# Power_Supply.net
KiCad netlist of a schematic drawn in Altium Designer
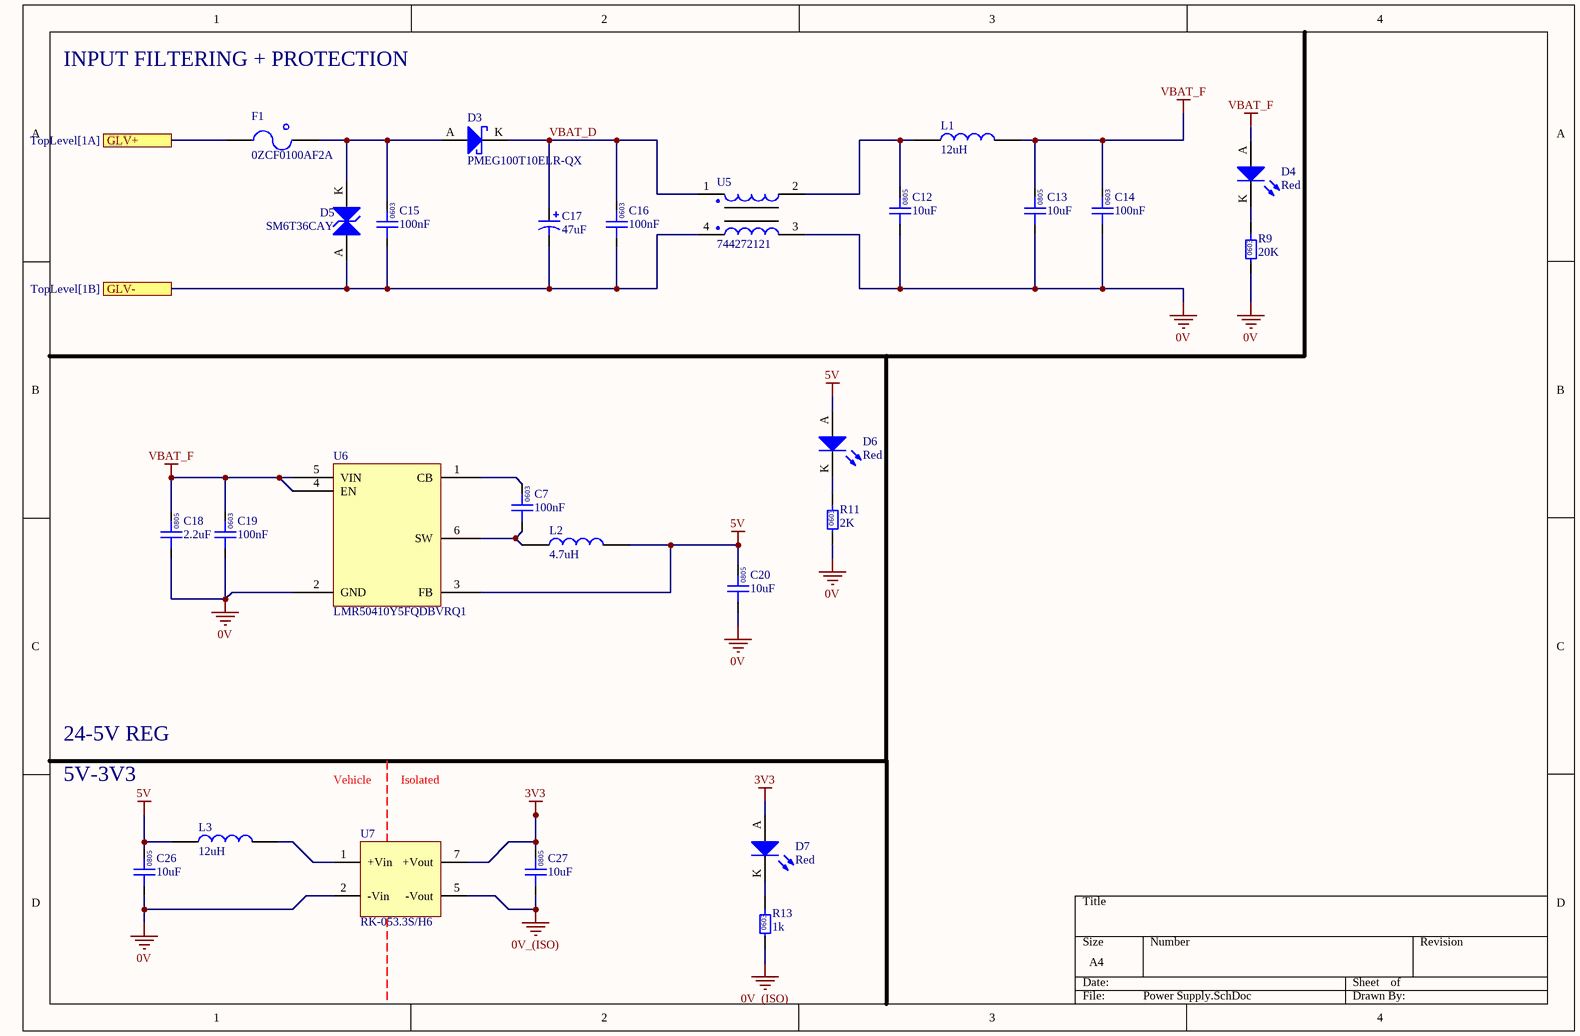
[diagram p0: Power Supply.SchDoc]

(export (version "E")
  (design (tool "Eeschema 10.0.6"))
  (components
    (comp (ref "C7")
      (value "100nF")
      (footprint "0603")
      (fields
        (field (name "PART NUMBER") "GCM188L81H104KA57D")
        (field (name "MANUFACTURER") "muRata")
        (field (name "TOLERANCE") "±10%")
      )
      (libsource (lib "ts_standard_library") (part "Capacitor 0603"))
    )
    (comp (ref "C12")
      (value "10uF")
      (footprint "0805")
      (fields
        (field (name "PART NUMBER") "GRM21BR6YA106KE43L")
        (field (name "MANUFACTURER") "muRata")
        (field (name "TOLERANCE") "10%")
      )
      (libsource (lib "ts_standard_library") (part "Capacitor 0805"))
    )
    (comp (ref "C13")
      (value "10uF")
      (footprint "0805")
      (fields
        (field (name "PART NUMBER") "GRM21BR6YA106KE43L")
        (field (name "MANUFACTURER") "muRata")
        (field (name "TOLERANCE") "10%")
      )
      (libsource (lib "ts_standard_library") (part "Capacitor 0805"))
    )
    (comp (ref "C14")
      (value "100nF")
      (footprint "0603")
      (fields
        (field (name "PART NUMBER") "GCM188L81H104KA57D")
        (field (name "MANUFACTURER") "muRata")
        (field (name "TOLERANCE") "±10%")
      )
      (libsource (lib "ts_standard_library") (part "Capacitor 0603"))
    )
    (comp (ref "C15")
      (value "100nF")
      (footprint "0603")
      (fields
        (field (name "PART NUMBER") "GCM188L81H104KA57D")
        (field (name "MANUFACTURER") "muRata")
        (field (name "TOLERANCE") "±10%")
      )
      (libsource (lib "ts_standard_library") (part "Capacitor 0603"))
    )
    (comp (ref "C16")
      (value "100nF")
      (footprint "0603")
      (fields
        (field (name "PART NUMBER") "GCM188L81H104KA57D")
        (field (name "MANUFACTURER") "muRata")
        (field (name "TOLERANCE") "±10%")
      )
      (libsource (lib "ts_standard_library") (part "Capacitor 0603"))
    )
    (comp (ref "C17")
      (value "47uF")
      (footprint "CHEMI-CON ELCO")
      (fields (field (name "PART NUMBER") "HHXA350ARA470MF61G"))
      (libsource (lib "ts_standard_library") (part "Capacitor (Polarised)"))
    )
    (comp (ref "C18")
      (value "2.2uF")
      (footprint "0805")
      (fields
        (field (name "PART NUMBER") "GRM21BR71E225KE11L")
        (field (name "MANUFACTURER") "Murata Electronics")
        (field (name "TOLERANCE") "±10%")
      )
      (libsource (lib "ts_standard_library") (part "Capacitor 0805"))
    )
    (comp (ref "C19")
      (value "100nF")
      (footprint "0603")
      (fields
        (field (name "PART NUMBER") "GCM188L81H104KA57D")
        (field (name "MANUFACTURER") "muRata")
        (field (name "TOLERANCE") "±10%")
      )
      (libsource (lib "ts_standard_library") (part "Capacitor 0603"))
    )
    (comp (ref "C20")
      (value "10uF")
      (footprint "0805")
      (fields
        (field (name "PART NUMBER") "GRM21BR6YA106KE43L")
        (field (name "MANUFACTURER") "muRata")
        (field (name "TOLERANCE") "10%")
      )
      (libsource (lib "ts_standard_library") (part "Capacitor 0805"))
    )
    (comp (ref "C26")
      (value "10uF")
      (footprint "0805")
      (fields
        (field (name "PART NUMBER") "GRM21BR6YA106KE43L")
        (field (name "MANUFACTURER") "muRata")
        (field (name "TOLERANCE") "10%")
      )
      (libsource (lib "ts_standard_library") (part "Capacitor 0805"))
    )
    (comp (ref "C27")
      (value "10uF")
      (footprint "0805")
      (fields
        (field (name "PART NUMBER") "GRM21BR6YA106KE43L")
        (field (name "MANUFACTURER") "muRata")
        (field (name "TOLERANCE") "10%")
      )
      (libsource (lib "ts_standard_library") (part "Capacitor 0805"))
    )
    (comp (ref "D3")
      (value "PMEG100T10ELR-QX")
      (footprint "NXP SOD123W")
      (fields
        (field (name "MANUFACTURER") "Nexperia USA Inc.")
        (field (name "DIGIKEY PART NUMBER") "1727-PMEG100T10ELR-QXCT-ND")
      )
      (libsource (lib "ts_standard_library") (part "Diode (Schottky)"))
    )
    (comp (ref "D4")
      (value "Red")
      (footprint "0805 LED")
      (description "Red LED Indication - Discrete 1.75V 0805 (2012 Metric)")
      (fields (field (name "PART NUMBER") "SML-210LTT86") (field (name "MANUFACTURER") "ROHM Semiconductor"))
      (libsource (lib "ts_standard_library") (part "LED"))
    )
    (comp (ref "D5")
      (value "SM6T36CAY")
      (footprint "ST SMB DIODE")
      (fields
        (field (name "MANUFACTURER") "STMicroelectronics")
        (field (name "DIGIKEY PART NUMBER") "497-10804-1-ND")
      )
      (libsource (lib "ts_standard_library") (part "TVS (Bidirectional)"))
    )
    (comp (ref "D6")
      (value "Red")
      (footprint "0805 LED")
      (description "Red LED Indication - Discrete 1.75V 0805 (2012 Metric)")
      (fields (field (name "PART NUMBER") "SML-210LTT86") (field (name "MANUFACTURER") "ROHM Semiconductor"))
      (libsource (lib "ts_standard_library") (part "LED"))
    )
    (comp (ref "D7")
      (value "Red")
      (footprint "0805 LED")
      (description "Red LED Indication - Discrete 1.75V 0805 (2012 Metric)")
      (fields (field (name "PART NUMBER") "SML-210LTT86") (field (name "MANUFACTURER") "ROHM Semiconductor"))
      (libsource (lib "ts_standard_library") (part "LED"))
    )
    (comp (ref "F1")
      (value "0ZCF0100AF2A")
      (footprint "2920")
      (description "PTC RESET FUSE 60V 1A 292")
      (fields
        (field (name "MANUFACTURER") "Littelfuse Inc.")
        (field (name "DIGIKEY PART NUMBER") "507-2070-1-ND")
      )
      (libsource (lib "ts_standard_library") (part "PTC Fuse"))
    )
    (comp (ref "L1")
      (value "12uH")
      (footprint "1812")
      (fields
        (field (name "PART NUMBER") "RLS-126")
        (field (name "MANUFACTURER") "Recom")
        (field (name "TOLERANCE") "0.2")
      )
      (libsource (lib "ts_20-standard-library") (part "Inductor"))
    )
    (comp (ref "L2")
      (value "4.7uH")
      (footprint "SRN3015TA-4R7M")
      (fields
        (field (name "PART NUMBER") "SRN4018-4R7M")
        (field (name "MANUFACTURER") "Bourns")
        (field (name "TOLERANCE") "0.2")
      )
      (libsource (lib "ts_standard_library") (part "Inductor"))
    )
    (comp (ref "L3")
      (value "12uH")
      (footprint "1812")
      (fields
        (field (name "PART NUMBER") "RLS-126")
        (field (name "MANUFACTURER") "Recom")
        (field (name "TOLERANCE") "0.2")
      )
      (libsource (lib "ts_standard_library") (part "Inductor"))
    )
    (comp (ref "R9")
      (value "20K")
      (footprint "0603")
      (fields
        (field (name "PART NUMBER") "RC0603FR-0720KL")
        (field (name "MANUFACTURER") "YAGEO")
        (field (name "TOLERANCE") "0.01")
      )
      (libsource (lib "ts_standard_library") (part "Resistor 0603"))
    )
    (comp (ref "R11")
      (value "2K")
      (footprint "0603")
      (fields
        (field (name "PART NUMBER") "RC0603FR-072KL")
        (field (name "MANUFACTURER") "YAGEO")
        (field (name "TOLERANCE") "0.01")
      )
      (libsource (lib "ts_standard_library") (part "Resistor 0603"))
    )
    (comp (ref "R13")
      (value "1k")
      (footprint "0603")
      (fields
        (field (name "PART NUMBER") "RC0603FR-071KL")
        (field (name "MANUFACTURER") "YAGEO")
        (field (name "TOLERANCE") "0.01")
      )
      (libsource (lib "ts_standard_library") (part "Resistor 0603"))
    )
    (comp (ref "U5")
      (value "744272121")
      (footprint "Wurth 4-PC Pad")
      (fields
        (field (name "MANUFACTURER") "Wurth Electronics Inc")
        (field (name "DIGIKEY PART NUMBER") "732-1489-1-ND")
      )
      (libsource (lib "ts_standard_library") (part "CM Choke"))
    )
    (comp (ref "U6")
      (value "LMR50410Y5FQDBVRQ1")
      (footprint "TI-SOT23-6")
      (description "IC REG BUCK 5V 1A SOT23-6")
      (fields (field (name "PART NUMBER") "LMR50410-Q1") (field (name "MANUFACTURER") "Texas Instruments"))
      (libsource (lib "ts_standard_library") (part "LMR50410Y5FQDBVRQ1"))
    )
    (comp (ref "U7")
      (value "RK-053.3S/H6")
      (footprint "RK-053.3S/H6")
      (description "DC DC CONVERTER 3.3V 1W")
      (fields (field (name "MANUFACTURER") "Recom"))
      (libsource (lib "ts_standard_library") (part "RK-053.3S/H6"))
    )
  )
  (nets
    (net (code "1") (name "/GLV+") (class "Default")
      (node (ref "F1") (pin "1") (pinfunction "1_1") (pintype "passive"))
    )
    (net (code "2") (name "/GLV-") (class "Default")
      (node (ref "C15") (pin "1") (pinfunction "1_1") (pintype "passive"))
      (node (ref "C16") (pin "1") (pinfunction "1_1") (pintype "passive"))
      (node (ref "C17") (pin "1") (pinfunction "1_1") (pintype "passive"))
      (node (ref "D5") (pin "A") (pinfunction "A_A") (pintype "passive"))
      (node (ref "U5") (pin "4") (pinfunction "4_4") (pintype "passive"))
    )
    (net (code "3") (name "/VBAT_D") (class "Default")
      (node (ref "C16") (pin "2") (pinfunction "2_2") (pintype "passive"))
      (node (ref "C17") (pin "2") (pinfunction "2_2") (pintype "passive"))
      (node (ref "D3") (pin "K") (pinfunction "K_K") (pintype "passive"))
      (node (ref "U5") (pin "1") (pinfunction "1_1") (pintype "passive"))
    )
    (net (code "4") (name "0V") (class "Default")
      (node (ref "C12") (pin "1") (pinfunction "1_1") (pintype "passive"))
      (node (ref "C13") (pin "1") (pinfunction "1_1") (pintype "passive"))
      (node (ref "C14") (pin "1") (pinfunction "1_1") (pintype "passive"))
      (node (ref "C18") (pin "1") (pinfunction "1_1") (pintype "passive"))
      (node (ref "C19") (pin "1") (pinfunction "1_1") (pintype "passive"))
      (node (ref "C20") (pin "1") (pinfunction "1_1") (pintype "passive"))
      (node (ref "C26") (pin "1") (pinfunction "1_1") (pintype "passive"))
      (node (ref "R11") (pin "1") (pinfunction "1_1") (pintype "passive"))
      (node (ref "R9") (pin "1") (pinfunction "1_1") (pintype "passive"))
      (node (ref "U5") (pin "3") (pinfunction "3_3") (pintype "power_in"))
      (node (ref "U6") (pin "2") (pinfunction "GND_2") (pintype "passive"))
      (node (ref "U7") (pin "2") (pinfunction "-Vin_2") (pintype "power_in"))
    )
    (net (code "5") (name "0V_(ISO)") (class "Default")
      (node (ref "C27") (pin "1") (pinfunction "1_1") (pintype "passive"))
      (node (ref "R13") (pin "1") (pinfunction "1_1") (pintype "passive"))
      (node (ref "U7") (pin "5") (pinfunction "-Vout_5") (pintype "power_in"))
    )
    (net (code "6") (name "3V3") (class "Default")
      (node (ref "C27") (pin "2") (pinfunction "2_2") (pintype "passive"))
      (node (ref "D7") (pin "A") (pinfunction "A_A") (pintype "passive"))
      (node (ref "U7") (pin "7") (pinfunction "+Vout_7") (pintype "power_in"))
    )
    (net (code "7") (name "5V") (class "Default")
      (node (ref "C20") (pin "2") (pinfunction "2_2") (pintype "passive"))
      (node (ref "C26") (pin "2") (pinfunction "2_2") (pintype "passive"))
      (node (ref "D6") (pin "A") (pinfunction "A_A") (pintype "passive"))
      (node (ref "L2") (pin "1") (pinfunction "1_1") (pintype "passive"))
      (node (ref "L3") (pin "2") (pinfunction "2_2") (pintype "passive"))
      (node (ref "U6") (pin "3") (pinfunction "FB_3") (pintype "passive"))
    )
    (net (code "8") (name "Net-(C12-Pad2)") (class "Default")
      (node (ref "C12") (pin "2") (pinfunction "2_2") (pintype "passive"))
      (node (ref "L1") (pin "2") (pinfunction "2_2") (pintype "passive"))
      (node (ref "U5") (pin "2") (pinfunction "2_2") (pintype "passive"))
    )
    (net (code "9") (name "Net-(C15-Pad2)") (class "Default")
      (node (ref "C15") (pin "2") (pinfunction "2_2") (pintype "passive"))
      (node (ref "D3") (pin "A") (pinfunction "A_A") (pintype "passive"))
      (node (ref "D5") (pin "K") (pinfunction "K_K") (pintype "passive"))
      (node (ref "F1") (pin "2") (pinfunction "2_2") (pintype "passive"))
    )
    (net (code "10") (name "Net-(D4-PadK)") (class "Default")
      (node (ref "D4") (pin "K") (pinfunction "K_K") (pintype "passive"))
      (node (ref "R9") (pin "2") (pinfunction "2_2") (pintype "passive"))
    )
    (net (code "11") (name "Net-(D6-PadK)") (class "Default")
      (node (ref "D6") (pin "K") (pinfunction "K_K") (pintype "passive"))
      (node (ref "R11") (pin "2") (pinfunction "2_2") (pintype "passive"))
    )
    (net (code "12") (name "Net-(D7-PadK)") (class "Default")
      (node (ref "D7") (pin "K") (pinfunction "K_K") (pintype "passive"))
      (node (ref "R13") (pin "2") (pinfunction "2_2") (pintype "passive"))
    )
    (net (code "13") (name "Net-(U6-CB)") (class "Default")
      (node (ref "C7") (pin "2") (pinfunction "2_2") (pintype "passive"))
      (node (ref "U6") (pin "1") (pinfunction "CB_1") (pintype "passive"))
    )
    (net (code "14") (name "Net-(U6-SW)") (class "Default")
      (node (ref "C7") (pin "1") (pinfunction "1_1") (pintype "passive"))
      (node (ref "L2") (pin "2") (pinfunction "2_2") (pintype "passive"))
      (node (ref "U6") (pin "6") (pinfunction "SW_6") (pintype "passive"))
    )
    (net (code "15") (name "Net-(U7-+Vin)") (class "Default")
      (node (ref "L3") (pin "1") (pinfunction "1_1") (pintype "passive"))
      (node (ref "U7") (pin "1") (pinfunction "+Vin_1") (pintype "power_in"))
    )
    (net (code "16") (name "VBAT_F") (class "Default")
      (node (ref "C13") (pin "2") (pinfunction "2_2") (pintype "passive"))
      (node (ref "C14") (pin "2") (pinfunction "2_2") (pintype "passive"))
      (node (ref "C18") (pin "2") (pinfunction "2_2") (pintype "passive"))
      (node (ref "C19") (pin "2") (pinfunction "2_2") (pintype "passive"))
      (node (ref "D4") (pin "A") (pinfunction "A_A") (pintype "passive"))
      (node (ref "L1") (pin "1") (pinfunction "1_1") (pintype "passive"))
      (node (ref "U6") (pin "4") (pinfunction "EN_4") (pintype "passive"))
      (node (ref "U6") (pin "5") (pinfunction "VIN_5") (pintype "passive"))
    )
  )
)
